# thermometer.net
KiCad netlist of a schematic drawn in EAGLE
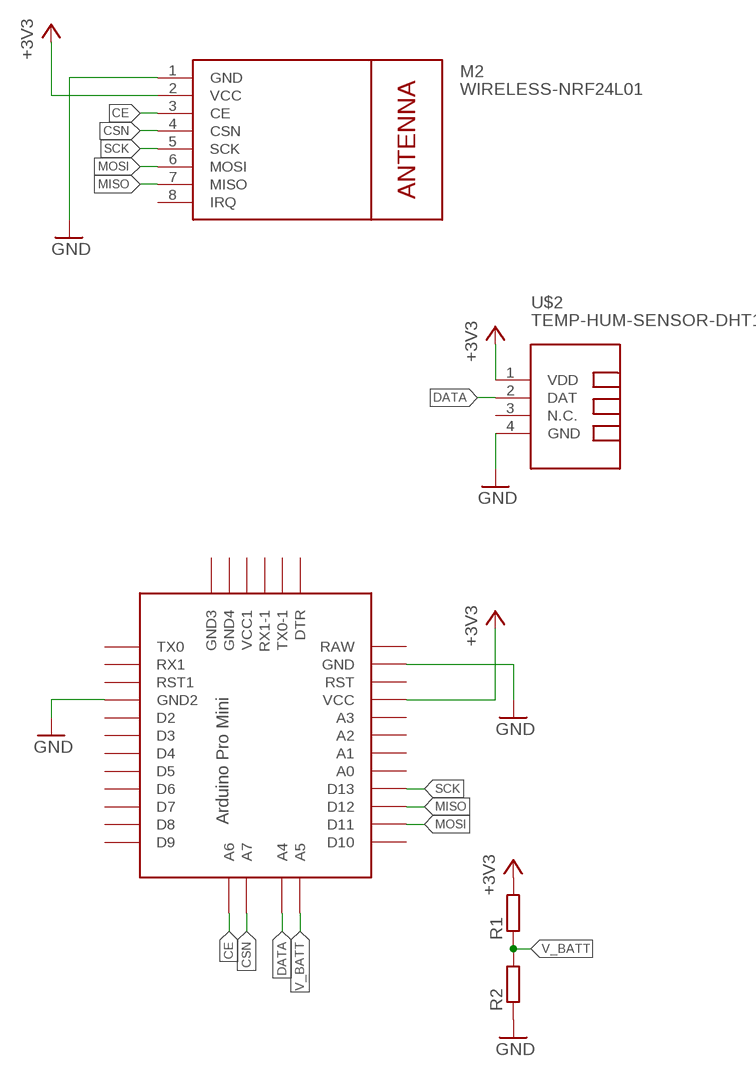
[diagram p0: schematic, sheet 1]

(export (version "E")
  (design (tool "Eeschema 10.0.6"))
  (components
    (comp (ref "M2")
      (value "WIRELESS-NRF24L01")
      (footprint "eagle-import:WIRELESS-NRF24L01")
      (libsource (lib "eagle-import") (part "WIRELESS-NRF24L01"))
    )
    (comp (ref "R1")
      (value "R-EU_R0805")
      (footprint "eagle-import:R0805")
      (libsource (lib "eagle-import") (part "R-EU_R0805"))
    )
    (comp (ref "R2")
      (value "R-EU_R0805")
      (footprint "eagle-import:R0805")
      (libsource (lib "eagle-import") (part "R-EU_R0805"))
    )
    (comp (ref "U$2")
      (value "TEMP-HUM-SENSOR-DHT11")
      (footprint "eagle-import:TEMP-HUM-SENSOR-DHT11")
      (libsource (lib "eagle-import") (part "TEMP-HUM-SENSOR-DHT11"))
    )
    (comp (ref "U$3")
      (value "PRO-MINI-2")
      (footprint "eagle-import:PRO-MINI-2")
      (libsource (lib "eagle-import") (part "PRO-MINI-2"))
    )
  )
  (nets
    (net (code "1") (name "+3V3") (class "Default")
      (node (ref "M2") (pin "2") (pinfunction "VCC_2") (pintype "power_in"))
      (node (ref "R1") (pin "2") (pinfunction "2_2") (pintype "passive"))
      (node (ref "U$2") (pin "1") (pinfunction "VDD_1") (pintype "power_in"))
      (node (ref "U$3") (pin "VCC") (pinfunction "VCC_VCC") (pintype "bidirectional"))
    )
    (net (code "2") (name "CE") (class "Default")
      (node (ref "M2") (pin "3") (pinfunction "CE_3") (pintype "bidirectional"))
      (node (ref "U$3") (pin "A6") (pinfunction "A6_A6") (pintype "bidirectional"))
    )
    (net (code "3") (name "CSN") (class "Default")
      (node (ref "M2") (pin "4") (pinfunction "CSN_4") (pintype "bidirectional"))
      (node (ref "U$3") (pin "A7") (pinfunction "A7_A7") (pintype "bidirectional"))
    )
    (net (code "4") (name "DATA") (class "Default")
      (node (ref "U$2") (pin "2") (pinfunction "DAT_2") (pintype "bidirectional"))
      (node (ref "U$3") (pin "A4") (pinfunction "A4_A4") (pintype "bidirectional"))
    )
    (net (code "5") (name "GND") (class "Default")
      (node (ref "M2") (pin "1") (pinfunction "GND_1") (pintype "power_in"))
      (node (ref "R2") (pin "1") (pinfunction "1_1") (pintype "passive"))
      (node (ref "U$2") (pin "4") (pinfunction "GND_4") (pintype "power_in"))
      (node (ref "U$3") (pin "GND") (pinfunction "GND_GND") (pintype "bidirectional"))
      (node (ref "U$3") (pin "GND1") (pinfunction "GND2_GND1") (pintype "bidirectional"))
    )
    (net (code "6") (name "MISO") (class "Default")
      (node (ref "M2") (pin "7") (pinfunction "MISO_7") (pintype "bidirectional"))
      (node (ref "U$3") (pin "D12") (pinfunction "D12_D12") (pintype "bidirectional"))
    )
    (net (code "7") (name "MOSI") (class "Default")
      (node (ref "M2") (pin "6") (pinfunction "MOSI_6") (pintype "bidirectional"))
      (node (ref "U$3") (pin "D11") (pinfunction "D11_D11") (pintype "bidirectional"))
    )
    (net (code "8") (name "SCK") (class "Default")
      (node (ref "M2") (pin "5") (pinfunction "SCK_5") (pintype "bidirectional"))
      (node (ref "U$3") (pin "D13") (pinfunction "D13_D13") (pintype "bidirectional"))
    )
    (net (code "9") (name "V_BATT") (class "Default")
      (node (ref "R1") (pin "1") (pinfunction "1_1") (pintype "passive"))
      (node (ref "R2") (pin "2") (pinfunction "2_2") (pintype "passive"))
      (node (ref "U$3") (pin "A5") (pinfunction "A5_A5") (pintype "bidirectional"))
    )
    (net (code "10") (name "unconnected-(M2-IRQ-Pad8)") (class "Default")
      (node (ref "M2") (pin "8") (pinfunction "IRQ_8") (pintype "bidirectional"))
    )
    (net (code "11") (name "unconnected-(U$2-N.C.-Pad3)") (class "Default")
      (node (ref "U$2") (pin "3") (pinfunction "N.C._3") (pintype "passive"))
    )
    (net (code "12") (name "unconnected-(U$3-GND3-PadGND2)") (class "Default")
      (node (ref "U$3") (pin "GND2") (pinfunction "GND3_GND2") (pintype "bidirectional"))
    )
    (net (code "13") (name "unconnected-(U$3-GND4-PadGND3)") (class "Default")
      (node (ref "U$3") (pin "GND3") (pinfunction "GND4_GND3") (pintype "bidirectional"))
    )
    (net (code "14") (name "unconnected-(U$3-PadA0)") (class "Default")
      (node (ref "U$3") (pin "A0") (pinfunction "A0_A0") (pintype "bidirectional"))
    )
    (net (code "15") (name "unconnected-(U$3-PadA1)") (class "Default")
      (node (ref "U$3") (pin "A1") (pinfunction "A1_A1") (pintype "bidirectional"))
    )
    (net (code "16") (name "unconnected-(U$3-PadA2)") (class "Default")
      (node (ref "U$3") (pin "A2") (pinfunction "A2_A2") (pintype "bidirectional"))
    )
    (net (code "17") (name "unconnected-(U$3-PadA3)") (class "Default")
      (node (ref "U$3") (pin "A3") (pinfunction "A3_A3") (pintype "bidirectional"))
    )
    (net (code "18") (name "unconnected-(U$3-PadD2)") (class "Default")
      (node (ref "U$3") (pin "D2") (pinfunction "D2_D2") (pintype "bidirectional"))
    )
    (net (code "19") (name "unconnected-(U$3-PadD3)") (class "Default")
      (node (ref "U$3") (pin "D3") (pinfunction "D3_D3") (pintype "bidirectional"))
    )
    (net (code "20") (name "unconnected-(U$3-PadD4)") (class "Default")
      (node (ref "U$3") (pin "D4") (pinfunction "D4_D4") (pintype "bidirectional"))
    )
    (net (code "21") (name "unconnected-(U$3-PadD5)") (class "Default")
      (node (ref "U$3") (pin "D5") (pinfunction "D5_D5") (pintype "bidirectional"))
    )
    (net (code "22") (name "unconnected-(U$3-PadD6)") (class "Default")
      (node (ref "U$3") (pin "D6") (pinfunction "D6_D6") (pintype "bidirectional"))
    )
    (net (code "23") (name "unconnected-(U$3-PadD7)") (class "Default")
      (node (ref "U$3") (pin "D7") (pinfunction "D7_D7") (pintype "bidirectional"))
    )
    (net (code "24") (name "unconnected-(U$3-PadD8)") (class "Default")
      (node (ref "U$3") (pin "D8") (pinfunction "D8_D8") (pintype "bidirectional"))
    )
    (net (code "25") (name "unconnected-(U$3-PadD9)") (class "Default")
      (node (ref "U$3") (pin "D9") (pinfunction "D9_D9") (pintype "bidirectional"))
    )
    (net (code "26") (name "unconnected-(U$3-PadD10)") (class "Default")
      (node (ref "U$3") (pin "D10") (pinfunction "D10_D10") (pintype "bidirectional"))
    )
    (net (code "27") (name "unconnected-(U$3-PadDTR)") (class "Default")
      (node (ref "U$3") (pin "DTR") (pinfunction "DTR_DTR") (pintype "bidirectional"))
    )
    (net (code "28") (name "unconnected-(U$3-PadRAW)") (class "Default")
      (node (ref "U$3") (pin "RAW") (pinfunction "RAW_RAW") (pintype "bidirectional"))
    )
    (net (code "29") (name "unconnected-(U$3-PadRST)") (class "Default")
      (node (ref "U$3") (pin "RST") (pinfunction "RST_RST") (pintype "bidirectional"))
    )
    (net (code "30") (name "unconnected-(U$3-PadRST1)") (class "Default")
      (node (ref "U$3") (pin "RST1") (pinfunction "RST1_RST1") (pintype "bidirectional"))
    )
    (net (code "31") (name "unconnected-(U$3-PadRX1)") (class "Default")
      (node (ref "U$3") (pin "RX1") (pinfunction "RX1_RX1") (pintype "bidirectional"))
    )
    (net (code "32") (name "unconnected-(U$3-PadRX1-1)") (class "Default")
      (node (ref "U$3") (pin "RX1-1") (pinfunction "RX1-1_RX1-1") (pintype "bidirectional"))
    )
    (net (code "33") (name "unconnected-(U$3-PadTX0)") (class "Default")
      (node (ref "U$3") (pin "TX0") (pinfunction "TX0_TX0") (pintype "bidirectional"))
    )
    (net (code "34") (name "unconnected-(U$3-PadTX0-1)") (class "Default")
      (node (ref "U$3") (pin "TX0-1") (pinfunction "TX0-1_TX0-1") (pintype "bidirectional"))
    )
    (net (code "35") (name "unconnected-(U$3-PadVCC1)") (class "Default")
      (node (ref "U$3") (pin "VCC1") (pinfunction "VCC1_VCC1") (pintype "bidirectional"))
    )
  )
)
